# Drive_Motors.net
KiCad netlist of a schematic drawn in Altium Designer
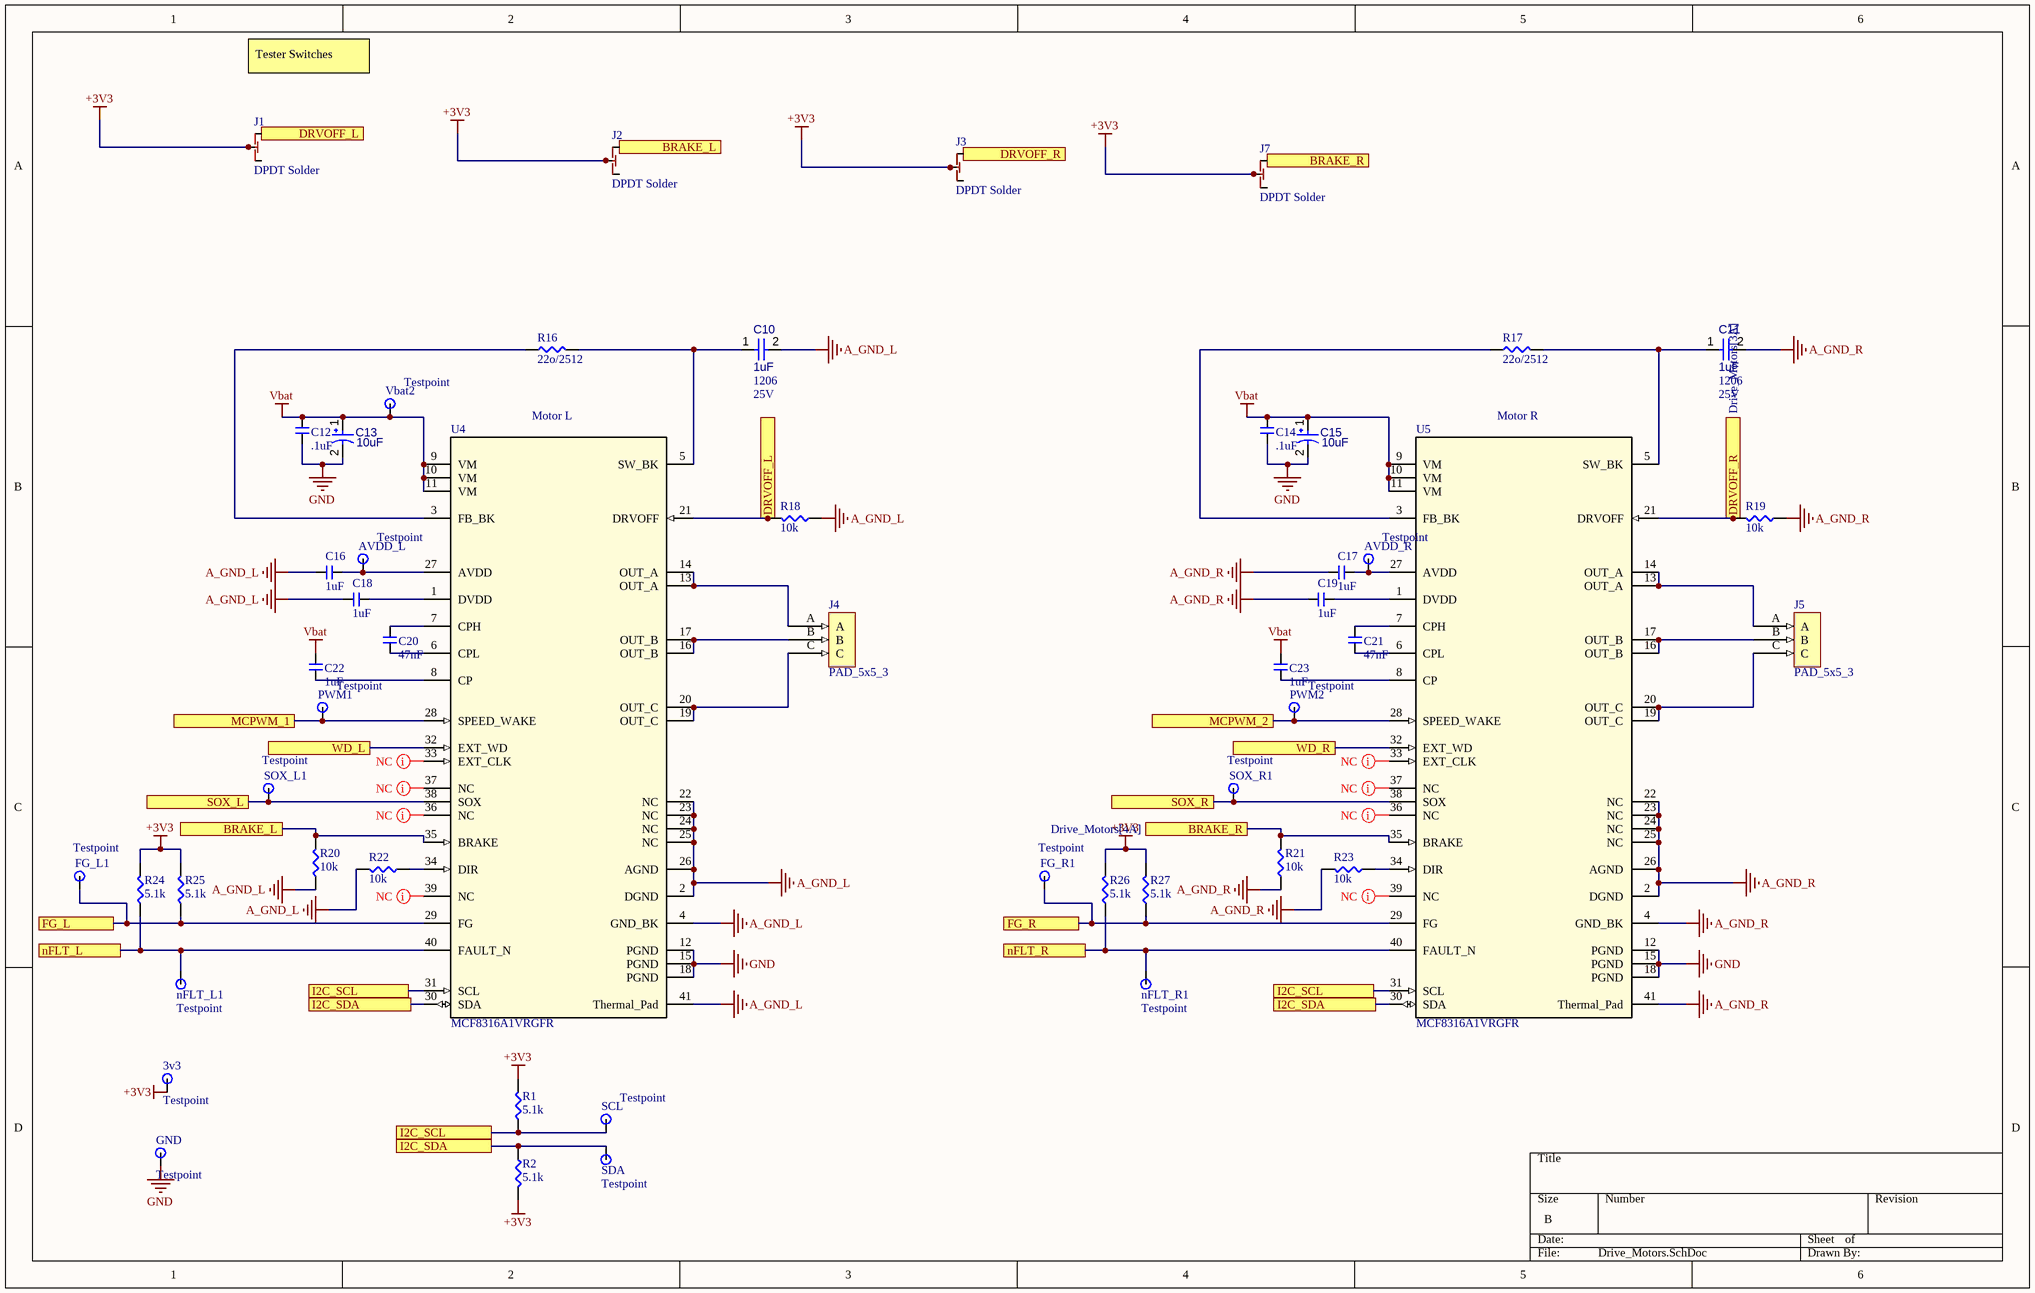
[diagram p0: Drive_Motors.SchDoc]

(export (version "E")
  (design (tool "Eeschema 10.0.6"))
  (components
    (comp (ref "3v3")
      (value "Testpoint")
      (footprint "Testpoint")
      (fields (field (name "SOURCE") "ife19_Elec_Library.SchLib"))
      (libsource (lib "Illini Formula Electric") (part "Testpoint"))
    )
    (comp (ref "AVDD_L")
      (value "Testpoint")
      (footprint "Testpoint")
      (fields (field (name "SOURCE") "ife19_Elec_Library.SchLib"))
      (libsource (lib "Illini Formula Electric") (part "Testpoint"))
    )
    (comp (ref "AVDD_R")
      (value "Testpoint")
      (footprint "Testpoint")
      (fields (field (name "SOURCE") "ife19_Elec_Library.SchLib"))
      (libsource (lib "Illini Formula Electric") (part "Testpoint"))
    )
    (comp (ref "C10")
      (value "1uF")
      (footprint "CAPC0603(1608)100_L")
      (description "Chip Capacitor, 1 uF, +/- 10%, 25 V, 1206 (3216 Metric)")
      (fields
        (field (name "PINS") "1206")
        (field (name "VOLTAGE RATING") "25V")
        (field (name "AVAILABLE PREVIEW IMAGES") "2D")
      )
      (libsource (lib "") (part "Symbol_1"))
    )
    (comp (ref "C11")
      (value "1uF")
      (footprint "CAPC0603(1608)100_L")
      (description "Chip Capacitor, 1 uF, +/- 10%, 25 V, 1206 (3216 Metric)")
      (fields
        (field (name "PINS") "1206")
        (field (name "VOLTAGE RATING") "25V")
        (field (name "AVAILABLE PREVIEW IMAGES") "2D")
      )
      (libsource (lib "") (part "Symbol_1"))
    )
    (comp (ref "C12")
      (value ".1uF")
      (footprint "CAP-0603")
      (description "X5R or X7R, 16V ceramic")
      (fields (field (name "SOURCE") "ife19_Elec_Library.SchLib"))
      (libsource (lib "Illini Formula Electric") (part "CAP-0603"))
    )
    (comp (ref "C13")
      (value "10uF")
      (footprint "EEF-CX1E330R-Footprint-1")
      (description "Aluminum Electrolytic Capacitor, 10 uF, +/- 20%, 50 V, -40 to 85 degC, 2-Pin THD, RoHS, Bulk")
      (fields (field (name "MANUFACTURER") "Panasonic"))
      (libsource (lib "") (part "Symbol_2"))
    )
    (comp (ref "C14")
      (value ".1uF")
      (footprint "CAP-0603")
      (description "X5R or X7R, 16V ceramic")
      (fields (field (name "SOURCE") "ife19_Elec_Library.SchLib"))
      (libsource (lib "Illini Formula Electric") (part "CAP-0603"))
    )
    (comp (ref "C15")
      (value "10uF")
      (footprint "EEF-CX1E330R-Footprint-1")
      (description "Aluminum Electrolytic Capacitor, 10 uF, +/- 20%, 50 V, -40 to 85 degC, 2-Pin THD, RoHS, Bulk")
      (fields (field (name "MANUFACTURER") "Panasonic"))
      (libsource (lib "") (part "Symbol_2"))
    )
    (comp (ref "C16")
      (value "1uF")
      (footprint "CAP-0603")
      (description "X5R or X7R, 16V ceramic")
      (fields (field (name "SOURCE") "ife19_Elec_Library.SchLib"))
      (libsource (lib "Illini Formula Electric") (part "CAP-0603"))
    )
    (comp (ref "C17")
      (value "1uF")
      (footprint "CAP-0603")
      (description "X5R or X7R, 16V ceramic")
      (fields (field (name "SOURCE") "ife19_Elec_Library.SchLib"))
      (libsource (lib "Illini Formula Electric") (part "CAP-0603"))
    )
    (comp (ref "C18")
      (value "1uF")
      (footprint "CAP-0603")
      (description "X5R or X7R, 16V ceramic")
      (fields (field (name "SOURCE") "ife19_Elec_Library.SchLib"))
      (libsource (lib "Illini Formula Electric") (part "CAP-0603"))
    )
    (comp (ref "C19")
      (value "1uF")
      (footprint "CAP-0603")
      (description "X5R or X7R, 16V ceramic")
      (fields (field (name "SOURCE") "ife19_Elec_Library.SchLib"))
      (libsource (lib "Illini Formula Electric") (part "CAP-0603"))
    )
    (comp (ref "C20")
      (value "47nF")
      (footprint "CAP-0603")
      (description "X5R or X7R, >32V ceramic")
      (fields (field (name "SOURCE") "ife19_Elec_Library.SchLib"))
      (libsource (lib "Illini Formula Electric") (part "CAP-0603"))
    )
    (comp (ref "C21")
      (value "47nF")
      (footprint "CAP-0603")
      (description "X5R or X7R, >32V ceramic")
      (fields (field (name "SOURCE") "ife19_Elec_Library.SchLib"))
      (libsource (lib "Illini Formula Electric") (part "CAP-0603"))
    )
    (comp (ref "C22")
      (value "1uF")
      (footprint "CAP-0603")
      (description "X5R or X7R, 16V ceramic")
      (fields (field (name "SOURCE") "ife19_Elec_Library.SchLib"))
      (libsource (lib "Illini Formula Electric") (part "CAP-0603"))
    )
    (comp (ref "C23")
      (value "1uF")
      (footprint "CAP-0603")
      (description "X5R or X7R, 16V ceramic")
      (fields (field (name "SOURCE") "ife19_Elec_Library.SchLib"))
      (libsource (lib "Illini Formula Electric") (part "CAP-0603"))
    )
    (comp (ref "FG_L1")
      (value "Testpoint")
      (footprint "Testpoint")
      (fields (field (name "SOURCE") "ife19_Elec_Library.SchLib"))
      (libsource (lib "Illini Formula Electric") (part "Testpoint"))
    )
    (comp (ref "FG_R1")
      (value "Testpoint")
      (footprint "Testpoint")
      (fields (field (name "SOURCE") "ife19_Elec_Library.SchLib"))
      (libsource (lib "Illini Formula Electric") (part "Testpoint"))
    )
    (comp (ref "GND")
      (value "Testpoint")
      (footprint "Testpoint")
      (fields (field (name "SOURCE") "ife19_Elec_Library.SchLib"))
      (libsource (lib "Illini Formula Electric") (part "Testpoint"))
    )
    (comp (ref "J1")
      (value "DPDT Solder")
      (footprint "DPDT Solder")
      (libsource (lib "Illini Formula Electric") (part "DPDT Solder"))
    )
    (comp (ref "J2")
      (value "DPDT Solder")
      (footprint "DPDT Solder")
      (libsource (lib "Illini Formula Electric") (part "DPDT Solder"))
    )
    (comp (ref "J3")
      (value "DPDT Solder")
      (footprint "DPDT Solder")
      (libsource (lib "Illini Formula Electric") (part "DPDT Solder"))
    )
    (comp (ref "J4")
      (value "PAD_5x5_3")
      (footprint "PAD_5x5_3-Footprint-1")
      (description "3 5x5mm pads")
      (libsource (lib "Illini Formula Electric") (part "PAD_5x5_3-Symbol-1"))
    )
    (comp (ref "J5")
      (value "PAD_5x5_3")
      (footprint "PAD_5x5_3-Footprint-1")
      (description "3 5x5mm pads")
      (libsource (lib "Illini Formula Electric") (part "PAD_5x5_3-Symbol-1"))
    )
    (comp (ref "J7")
      (value "DPDT Solder")
      (footprint "DPDT Solder")
      (libsource (lib "Illini Formula Electric") (part "DPDT Solder"))
    )
    (comp (ref "nFLT_L1")
      (value "Testpoint")
      (footprint "Testpoint")
      (fields (field (name "SOURCE") "ife19_Elec_Library.SchLib"))
      (libsource (lib "Illini Formula Electric") (part "Testpoint"))
    )
    (comp (ref "nFLT_R1")
      (value "Testpoint")
      (footprint "Testpoint")
      (fields (field (name "SOURCE") "ife19_Elec_Library.SchLib"))
      (libsource (lib "Illini Formula Electric") (part "Testpoint"))
    )
    (comp (ref "PWM1")
      (value "Testpoint")
      (footprint "Testpoint")
      (fields (field (name "SOURCE") "ife19_Elec_Library.SchLib"))
      (libsource (lib "Illini Formula Electric") (part "Testpoint"))
    )
    (comp (ref "PWM2")
      (value "Testpoint")
      (footprint "Testpoint")
      (fields (field (name "SOURCE") "ife19_Elec_Library.SchLib"))
      (libsource (lib "Illini Formula Electric") (part "Testpoint"))
    )
    (comp (ref "R1")
      (value "5.1k")
      (footprint "RES-0603")
      (fields (field (name "SOURCE") "ife19_Elec_Library.SchLib"))
      (libsource (lib "Illini Formula Electric") (part "Symbol"))
    )
    (comp (ref "R2")
      (value "5.1k")
      (footprint "RES-0603")
      (fields (field (name "SOURCE") "ife19_Elec_Library.SchLib"))
      (libsource (lib "Illini Formula Electric") (part "Symbol"))
    )
    (comp (ref "R16")
      (value "22o/2512")
      (footprint "RES-2512")
      (fields (field (name "SOURCE") "ife19_Elec_Library.SchLib"))
      (libsource (lib "Illini Formula Electric") (part "RES-AXIAL0.5"))
    )
    (comp (ref "R17")
      (value "22o/2512")
      (footprint "RES-2512")
      (fields (field (name "SOURCE") "ife19_Elec_Library.SchLib"))
      (libsource (lib "Illini Formula Electric") (part "RES-AXIAL0.5"))
    )
    (comp (ref "R18")
      (value "10k")
      (footprint "RES-0603")
      (fields (field (name "SOURCE") "ife19_Elec_Library.SchLib"))
      (libsource (lib "Illini Formula Electric") (part "Symbol"))
    )
    (comp (ref "R19")
      (value "10k")
      (footprint "RES-0603")
      (fields (field (name "SOURCE") "ife19_Elec_Library.SchLib"))
      (libsource (lib "Illini Formula Electric") (part "Symbol"))
    )
    (comp (ref "R20")
      (value "10k")
      (footprint "RES-0603")
      (fields (field (name "SOURCE") "ife19_Elec_Library.SchLib"))
      (libsource (lib "Illini Formula Electric") (part "Symbol"))
    )
    (comp (ref "R21")
      (value "10k")
      (footprint "RES-0603")
      (fields (field (name "SOURCE") "ife19_Elec_Library.SchLib"))
      (libsource (lib "Illini Formula Electric") (part "Symbol"))
    )
    (comp (ref "R22")
      (value "10k")
      (footprint "RES-0603")
      (fields (field (name "SOURCE") "ife19_Elec_Library.SchLib"))
      (libsource (lib "Illini Formula Electric") (part "Symbol"))
    )
    (comp (ref "R23")
      (value "10k")
      (footprint "RES-0603")
      (fields (field (name "SOURCE") "ife19_Elec_Library.SchLib"))
      (libsource (lib "Illini Formula Electric") (part "Symbol"))
    )
    (comp (ref "R24")
      (value "5.1k")
      (footprint "RES-0603")
      (fields (field (name "SOURCE") "ife19_Elec_Library.SchLib"))
      (libsource (lib "Illini Formula Electric") (part "Symbol"))
    )
    (comp (ref "R25")
      (value "5.1k")
      (footprint "RES-0603")
      (fields (field (name "SOURCE") "ife19_Elec_Library.SchLib"))
      (libsource (lib "Illini Formula Electric") (part "Symbol"))
    )
    (comp (ref "R26")
      (value "5.1k")
      (footprint "RES-0603")
      (fields (field (name "SOURCE") "ife19_Elec_Library.SchLib"))
      (libsource (lib "Illini Formula Electric") (part "Symbol"))
    )
    (comp (ref "R27")
      (value "5.1k")
      (footprint "RES-0603")
      (fields (field (name "SOURCE") "ife19_Elec_Library.SchLib"))
      (libsource (lib "Illini Formula Electric") (part "Symbol"))
    )
    (comp (ref "SCL")
      (value "Testpoint")
      (footprint "Testpoint")
      (fields (field (name "SOURCE") "ife19_Elec_Library.SchLib"))
      (libsource (lib "Illini Formula Electric") (part "Testpoint"))
    )
    (comp (ref "SDA")
      (value "Testpoint")
      (footprint "Testpoint")
      (fields (field (name "SOURCE") "ife19_Elec_Library.SchLib"))
      (libsource (lib "Illini Formula Electric") (part "Testpoint"))
    )
    (comp (ref "SOX_L1")
      (value "Testpoint")
      (footprint "Testpoint")
      (fields (field (name "SOURCE") "ife19_Elec_Library.SchLib"))
      (libsource (lib "Illini Formula Electric") (part "Testpoint"))
    )
    (comp (ref "SOX_R1")
      (value "Testpoint")
      (footprint "Testpoint")
      (fields (field (name "SOURCE") "ife19_Elec_Library.SchLib"))
      (libsource (lib "Illini Formula Electric") (part "Testpoint"))
    )
    (comp (ref "U4")
      (value "MCF8316A1VRGFR")
      (footprint "RGF0040E-IPC_A")
      (description "No Description Available")
      (libsource (lib "Illini Formula Electric") (part "MCF8316A1VRGFR"))
    )
    (comp (ref "U5")
      (value "MCF8316A1VRGFR")
      (footprint "RGF0040E-IPC_A")
      (description "No Description Available")
      (libsource (lib "Illini Formula Electric") (part "MCF8316A1VRGFR"))
    )
    (comp (ref "Vbat2")
      (value "Testpoint")
      (footprint "Testpoint")
      (fields (field (name "SOURCE") "ife19_Elec_Library.SchLib"))
      (libsource (lib "Illini Formula Electric") (part "Testpoint"))
    )
  )
  (nets
    (net (code "1") (name "+3V3") (class "Default")
      (node (ref "3v3") (pin "1") (pinfunction "1_1") (pintype "passive"))
      (node (ref "J1") (pin "3") (pintype "passive"))
      (node (ref "J2") (pin "3") (pintype "passive"))
      (node (ref "J3") (pin "3") (pintype "passive"))
      (node (ref "J7") (pin "3") (pintype "passive"))
      (node (ref "R1") (pin "2") (pinfunction "2_2") (pintype "passive"))
      (node (ref "R2") (pin "2") (pinfunction "2_2") (pintype "passive"))
      (node (ref "R24") (pin "2") (pinfunction "2_2") (pintype "passive"))
      (node (ref "R25") (pin "2") (pinfunction "2_2") (pintype "passive"))
      (node (ref "R26") (pin "2") (pinfunction "2_2") (pintype "passive"))
      (node (ref "R27") (pin "2") (pinfunction "2_2") (pintype "passive"))
    )
    (net (code "2") (name "/BRAKE_L") (class "Default")
      (node (ref "J2") (pin "1") (pintype "passive"))
      (node (ref "R20") (pin "2") (pinfunction "2_2") (pintype "passive"))
      (node (ref "U4") (pin "35") (pinfunction "BRAKE_35") (pintype "input"))
    )
    (net (code "3") (name "/BRAKE_R") (class "Default")
      (node (ref "J7") (pin "1") (pintype "passive"))
      (node (ref "R21") (pin "2") (pinfunction "2_2") (pintype "passive"))
      (node (ref "U5") (pin "35") (pinfunction "BRAKE_35") (pintype "input"))
    )
    (net (code "4") (name "/DRVOFF_L") (class "Default")
      (node (ref "J1") (pin "1") (pintype "passive"))
      (node (ref "R18") (pin "2") (pinfunction "2_2") (pintype "passive"))
      (node (ref "U4") (pin "21") (pinfunction "DRVOFF_21") (pintype "input"))
    )
    (net (code "5") (name "/DRVOFF_R") (class "Default")
      (node (ref "J3") (pin "1") (pintype "passive"))
      (node (ref "R19") (pin "2") (pinfunction "2_2") (pintype "passive"))
      (node (ref "U5") (pin "21") (pinfunction "DRVOFF_21") (pintype "input"))
    )
    (net (code "6") (name "/FG_L") (class "Default")
      (node (ref "FG_L1") (pin "1") (pinfunction "1_1") (pintype "passive"))
      (node (ref "R25") (pin "1") (pinfunction "1_1") (pintype "passive"))
      (node (ref "U4") (pin "29") (pinfunction "FG_29") (pintype "open_collector"))
    )
    (net (code "7") (name "/FG_R") (class "Default")
      (node (ref "FG_R1") (pin "1") (pinfunction "1_1") (pintype "passive"))
      (node (ref "R27") (pin "1") (pinfunction "1_1") (pintype "passive"))
      (node (ref "U5") (pin "29") (pinfunction "FG_29") (pintype "open_collector"))
    )
    (net (code "8") (name "/I2C_SCL") (class "Default")
      (node (ref "R1") (pin "1") (pinfunction "1_1") (pintype "passive"))
      (node (ref "SCL") (pin "1") (pinfunction "1_1") (pintype "passive"))
      (node (ref "U4") (pin "31") (pinfunction "SCL_31") (pintype "input"))
      (node (ref "U5") (pin "31") (pinfunction "SCL_31") (pintype "input"))
    )
    (net (code "9") (name "/I2C_SDA") (class "Default")
      (node (ref "R2") (pin "1") (pinfunction "1_1") (pintype "passive"))
      (node (ref "SDA") (pin "1") (pinfunction "1_1") (pintype "passive"))
      (node (ref "U4") (pin "30") (pinfunction "SDA_30") (pintype "bidirectional"))
      (node (ref "U5") (pin "30") (pinfunction "SDA_30") (pintype "bidirectional"))
    )
    (net (code "10") (name "/MCPWM_1") (class "Default")
      (node (ref "PWM1") (pin "1") (pinfunction "1_1") (pintype "passive"))
      (node (ref "U4") (pin "28") (pinfunction "SPEED_WAKE_28") (pintype "input"))
    )
    (net (code "11") (name "/MCPWM_2") (class "Default")
      (node (ref "PWM2") (pin "1") (pinfunction "1_1") (pintype "passive"))
      (node (ref "U5") (pin "28") (pinfunction "SPEED_WAKE_28") (pintype "input"))
    )
    (net (code "12") (name "/SOX_L") (class "Default")
      (node (ref "SOX_L1") (pin "1") (pinfunction "1_1") (pintype "passive"))
      (node (ref "U4") (pin "38") (pinfunction "SOX_38") (pintype "passive"))
    )
    (net (code "13") (name "/SOX_R") (class "Default")
      (node (ref "SOX_R1") (pin "1") (pinfunction "1_1") (pintype "passive"))
      (node (ref "U5") (pin "38") (pinfunction "SOX_38") (pintype "passive"))
    )
    (net (code "14") (name "/WD_L") (class "Default")
      (node (ref "U4") (pin "32") (pinfunction "EXT_WD_32") (pintype "input"))
    )
    (net (code "15") (name "/WD_R") (class "Default")
      (node (ref "U5") (pin "32") (pinfunction "EXT_WD_32") (pintype "input"))
    )
    (net (code "16") (name "/nFLT_L") (class "Default")
      (node (ref "R24") (pin "1") (pinfunction "1_1") (pintype "passive"))
      (node (ref "U4") (pin "40") (pinfunction "FAULT_N_40") (pintype "open_collector"))
      (node (ref "nFLT_L1") (pin "1") (pinfunction "1_1") (pintype "passive"))
    )
    (net (code "17") (name "/nFLT_R") (class "Default")
      (node (ref "R26") (pin "1") (pinfunction "1_1") (pintype "passive"))
      (node (ref "U5") (pin "40") (pinfunction "FAULT_N_40") (pintype "open_collector"))
      (node (ref "nFLT_R1") (pin "1") (pinfunction "1_1") (pintype "passive"))
    )
    (net (code "18") (name "A_GND_L") (class "Default")
      (node (ref "C10") (pin "2") (pinfunction "2_2") (pintype "passive"))
      (node (ref "C16") (pin "2") (pinfunction "2_2") (pintype "passive"))
      (node (ref "C18") (pin "2") (pinfunction "2_2") (pintype "passive"))
      (node (ref "R18") (pin "1") (pinfunction "1_1") (pintype "passive"))
      (node (ref "R20") (pin "1") (pinfunction "1_1") (pintype "passive"))
      (node (ref "R22") (pin "2") (pinfunction "2_2") (pintype "passive"))
      (node (ref "U4") (pin "2") (pinfunction "DGND_2") (pintype "power_in"))
      (node (ref "U4") (pin "22") (pinfunction "NC_22") (pintype "passive"))
      (node (ref "U4") (pin "23") (pinfunction "NC_23") (pintype "passive"))
      (node (ref "U4") (pin "24") (pinfunction "NC_24") (pintype "passive"))
      (node (ref "U4") (pin "25") (pinfunction "NC_25") (pintype "passive"))
      (node (ref "U4") (pin "26") (pinfunction "AGND_26") (pintype "power_in"))
      (node (ref "U4") (pin "4") (pinfunction "GND_BK_4") (pintype "power_in"))
      (node (ref "U4") (pin "41") (pinfunction "Thermal_Pad_41") (pintype "power_in"))
    )
    (net (code "19") (name "A_GND_R") (class "Default")
      (node (ref "C11") (pin "2") (pinfunction "2_2") (pintype "passive"))
      (node (ref "C17") (pin "2") (pinfunction "2_2") (pintype "passive"))
      (node (ref "C19") (pin "2") (pinfunction "2_2") (pintype "passive"))
      (node (ref "R19") (pin "1") (pinfunction "1_1") (pintype "passive"))
      (node (ref "R21") (pin "1") (pinfunction "1_1") (pintype "passive"))
      (node (ref "R23") (pin "2") (pinfunction "2_2") (pintype "passive"))
      (node (ref "U5") (pin "2") (pinfunction "DGND_2") (pintype "power_in"))
      (node (ref "U5") (pin "22") (pinfunction "NC_22") (pintype "passive"))
      (node (ref "U5") (pin "23") (pinfunction "NC_23") (pintype "passive"))
      (node (ref "U5") (pin "24") (pinfunction "NC_24") (pintype "passive"))
      (node (ref "U5") (pin "25") (pinfunction "NC_25") (pintype "passive"))
      (node (ref "U5") (pin "26") (pinfunction "AGND_26") (pintype "power_in"))
      (node (ref "U5") (pin "4") (pinfunction "GND_BK_4") (pintype "power_in"))
      (node (ref "U5") (pin "41") (pinfunction "Thermal_Pad_41") (pintype "power_in"))
    )
    (net (code "20") (name "GND") (class "Default")
      (node (ref "C12") (pin "1") (pinfunction "1_1") (pintype "passive"))
      (node (ref "C13") (pin "2") (pinfunction "2_2") (pintype "passive"))
      (node (ref "C14") (pin "1") (pinfunction "1_1") (pintype "passive"))
      (node (ref "C15") (pin "2") (pinfunction "2_2") (pintype "passive"))
      (node (ref "GND") (pin "1") (pinfunction "1_1") (pintype "passive"))
      (node (ref "U4") (pin "12") (pinfunction "PGND_12") (pintype "power_in"))
      (node (ref "U4") (pin "15") (pinfunction "PGND_15") (pintype "power_in"))
      (node (ref "U4") (pin "18") (pinfunction "PGND_18") (pintype "power_in"))
      (node (ref "U5") (pin "12") (pinfunction "PGND_12") (pintype "power_in"))
      (node (ref "U5") (pin "15") (pinfunction "PGND_15") (pintype "power_in"))
      (node (ref "U5") (pin "18") (pinfunction "PGND_18") (pintype "power_in"))
    )
    (net (code "21") (name "Net-(J4-PadA)") (class "Default")
      (node (ref "J4") (pin "A") (pinfunction "A_A") (pintype "input"))
      (node (ref "U4") (pin "13") (pinfunction "OUT_A_13") (pintype "passive"))
      (node (ref "U4") (pin "14") (pinfunction "OUT_A_14") (pintype "passive"))
    )
    (net (code "22") (name "Net-(J4-PadB)") (class "Default")
      (node (ref "J4") (pin "B") (pinfunction "B_B") (pintype "input"))
      (node (ref "U4") (pin "16") (pinfunction "OUT_B_16") (pintype "passive"))
      (node (ref "U4") (pin "17") (pinfunction "OUT_B_17") (pintype "passive"))
    )
    (net (code "23") (name "Net-(J4-PadC)") (class "Default")
      (node (ref "J4") (pin "C") (pinfunction "C_C") (pintype "input"))
      (node (ref "U4") (pin "19") (pinfunction "OUT_C_19") (pintype "passive"))
      (node (ref "U4") (pin "20") (pinfunction "OUT_C_20") (pintype "passive"))
    )
    (net (code "24") (name "Net-(J5-PadA)") (class "Default")
      (node (ref "J5") (pin "A") (pinfunction "A_A") (pintype "input"))
      (node (ref "U5") (pin "13") (pinfunction "OUT_A_13") (pintype "passive"))
      (node (ref "U5") (pin "14") (pinfunction "OUT_A_14") (pintype "passive"))
    )
    (net (code "25") (name "Net-(J5-PadB)") (class "Default")
      (node (ref "J5") (pin "B") (pinfunction "B_B") (pintype "input"))
      (node (ref "U5") (pin "16") (pinfunction "OUT_B_16") (pintype "passive"))
      (node (ref "U5") (pin "17") (pinfunction "OUT_B_17") (pintype "passive"))
    )
    (net (code "26") (name "Net-(J5-PadC)") (class "Default")
      (node (ref "J5") (pin "C") (pinfunction "C_C") (pintype "input"))
      (node (ref "U5") (pin "19") (pinfunction "OUT_C_19") (pintype "passive"))
      (node (ref "U5") (pin "20") (pinfunction "OUT_C_20") (pintype "passive"))
    )
    (net (code "27") (name "Net-(U4-AVDD)") (class "Default")
      (node (ref "AVDD_L") (pin "1") (pinfunction "1_1") (pintype "passive"))
      (node (ref "C16") (pin "1") (pinfunction "1_1") (pintype "passive"))
      (node (ref "U4") (pin "27") (pinfunction "AVDD_27") (pintype "power_in"))
    )
    (net (code "28") (name "Net-(U4-CP)") (class "Default")
      (node (ref "C22") (pin "1") (pinfunction "1_1") (pintype "passive"))
      (node (ref "U4") (pin "8") (pinfunction "CP_8") (pintype "passive"))
    )
    (net (code "29") (name "Net-(U4-CPH)") (class "Default")
      (node (ref "C20") (pin "1") (pinfunction "1_1") (pintype "passive"))
      (node (ref "U4") (pin "7") (pinfunction "CPH_7") (pintype "passive"))
    )
    (net (code "30") (name "Net-(U4-CPL)") (class "Default")
      (node (ref "C20") (pin "2") (pinfunction "2_2") (pintype "passive"))
      (node (ref "U4") (pin "6") (pinfunction "CPL_6") (pintype "passive"))
    )
    (net (code "31") (name "Net-(U4-DIR)") (class "Default")
      (node (ref "R22") (pin "1") (pinfunction "1_1") (pintype "passive"))
      (node (ref "U4") (pin "34") (pinfunction "DIR_34") (pintype "input"))
    )
    (net (code "32") (name "Net-(U4-DVDD)") (class "Default")
      (node (ref "C18") (pin "1") (pinfunction "1_1") (pintype "passive"))
      (node (ref "U4") (pin "1") (pinfunction "DVDD_1") (pintype "power_in"))
    )
    (net (code "33") (name "Net-(U4-FB_BK)") (class "Default")
      (node (ref "R16") (pin "1") (pinfunction "1_1") (pintype "passive"))
      (node (ref "U4") (pin "3") (pinfunction "FB_BK_3") (pintype "passive"))
    )
    (net (code "34") (name "Net-(U4-SW_BK)") (class "Default")
      (node (ref "C10") (pin "1") (pinfunction "1_1") (pintype "passive"))
      (node (ref "R16") (pin "2") (pinfunction "2_2") (pintype "passive"))
      (node (ref "U4") (pin "5") (pinfunction "SW_BK_5") (pintype "power_in"))
    )
    (net (code "35") (name "Net-(U5-AVDD)") (class "Default")
      (node (ref "AVDD_R") (pin "1") (pinfunction "1_1") (pintype "passive"))
      (node (ref "C17") (pin "1") (pinfunction "1_1") (pintype "passive"))
      (node (ref "U5") (pin "27") (pinfunction "AVDD_27") (pintype "power_in"))
    )
    (net (code "36") (name "Net-(U5-CP)") (class "Default")
      (node (ref "C23") (pin "1") (pinfunction "1_1") (pintype "passive"))
      (node (ref "U5") (pin "8") (pinfunction "CP_8") (pintype "passive"))
    )
    (net (code "37") (name "Net-(U5-CPH)") (class "Default")
      (node (ref "C21") (pin "1") (pinfunction "1_1") (pintype "passive"))
      (node (ref "U5") (pin "7") (pinfunction "CPH_7") (pintype "passive"))
    )
    (net (code "38") (name "Net-(U5-CPL)") (class "Default")
      (node (ref "C21") (pin "2") (pinfunction "2_2") (pintype "passive"))
      (node (ref "U5") (pin "6") (pinfunction "CPL_6") (pintype "passive"))
    )
    (net (code "39") (name "Net-(U5-DIR)") (class "Default")
      (node (ref "R23") (pin "1") (pinfunction "1_1") (pintype "passive"))
      (node (ref "U5") (pin "34") (pinfunction "DIR_34") (pintype "input"))
    )
    (net (code "40") (name "Net-(U5-DVDD)") (class "Default")
      (node (ref "C19") (pin "1") (pinfunction "1_1") (pintype "passive"))
      (node (ref "U5") (pin "1") (pinfunction "DVDD_1") (pintype "power_in"))
    )
    (net (code "41") (name "Net-(U5-FB_BK)") (class "Default")
      (node (ref "R17") (pin "1") (pinfunction "1_1") (pintype "passive"))
      (node (ref "U5") (pin "3") (pinfunction "FB_BK_3") (pintype "passive"))
    )
    (net (code "42") (name "Net-(U5-SW_BK)") (class "Default")
      (node (ref "C11") (pin "1") (pinfunction "1_1") (pintype "passive"))
      (node (ref "R17") (pin "2") (pinfunction "2_2") (pintype "passive"))
      (node (ref "U5") (pin "5") (pinfunction "SW_BK_5") (pintype "power_in"))
    )
    (net (code "43") (name "Vbat") (class "Default")
      (node (ref "C12") (pin "2") (pinfunction "2_2") (pintype "passive"))
      (node (ref "C13") (pin "1") (pinfunction "1_1") (pintype "passive"))
      (node (ref "C14") (pin "2") (pinfunction "2_2") (pintype "passive"))
      (node (ref "C15") (pin "1") (pinfunction "1_1") (pintype "passive"))
      (node (ref "C22") (pin "2") (pinfunction "2_2") (pintype "passive"))
      (node (ref "C23") (pin "2") (pinfunction "2_2") (pintype "passive"))
      (node (ref "U4") (pin "10") (pinfunction "VM_10") (pintype "power_in"))
      (node (ref "U4") (pin "11") (pinfunction "VM_11") (pintype "power_in"))
      (node (ref "U4") (pin "9") (pinfunction "VM_9") (pintype "power_in"))
      (node (ref "U5") (pin "10") (pinfunction "VM_10") (pintype "power_in"))
      (node (ref "U5") (pin "11") (pinfunction "VM_11") (pintype "power_in"))
      (node (ref "U5") (pin "9") (pinfunction "VM_9") (pintype "power_in"))
      (node (ref "Vbat2") (pin "1") (pinfunction "1_1") (pintype "passive"))
    )
    (net (code "44") (name "unconnected-(J1-Pad2)") (class "Default")
      (node (ref "J1") (pin "2") (pintype "passive"))
    )
    (net (code "45") (name "unconnected-(J2-Pad2)") (class "Default")
      (node (ref "J2") (pin "2") (pintype "passive"))
    )
    (net (code "46") (name "unconnected-(J3-Pad2)") (class "Default")
      (node (ref "J3") (pin "2") (pintype "passive"))
    )
    (net (code "47") (name "unconnected-(J7-Pad2)") (class "Default")
      (node (ref "J7") (pin "2") (pintype "passive"))
    )
    (net (code "48") (name "unconnected-(U4-EXT_CLK-Pad33)") (class "Default")
      (node (ref "U4") (pin "33") (pinfunction "EXT_CLK_33") (pintype "input"))
    )
    (net (code "49") (name "unconnected-(U4-NC-Pad36)") (class "Default")
      (node (ref "U4") (pin "36") (pinfunction "NC_36") (pintype "passive"))
    )
    (net (code "50") (name "unconnected-(U4-NC-Pad37)") (class "Default")
      (node (ref "U4") (pin "37") (pinfunction "NC_37") (pintype "passive"))
    )
    (net (code "51") (name "unconnected-(U4-NC-Pad39)") (class "Default")
      (node (ref "U4") (pin "39") (pinfunction "NC_39") (pintype "passive"))
    )
    (net (code "52") (name "unconnected-(U5-EXT_CLK-Pad33)") (class "Default")
      (node (ref "U5") (pin "33") (pinfunction "EXT_CLK_33") (pintype "input"))
    )
    (net (code "53") (name "unconnected-(U5-NC-Pad36)") (class "Default")
      (node (ref "U5") (pin "36") (pinfunction "NC_36") (pintype "passive"))
    )
    (net (code "54") (name "unconnected-(U5-NC-Pad37)") (class "Default")
      (node (ref "U5") (pin "37") (pinfunction "NC_37") (pintype "passive"))
    )
    (net (code "55") (name "unconnected-(U5-NC-Pad39)") (class "Default")
      (node (ref "U5") (pin "39") (pinfunction "NC_39") (pintype "passive"))
    )
  )
)
